# oshi-fuse-board-mk-1_3-mini-ato.net
KiCad netlist of a schematic drawn in EAGLE
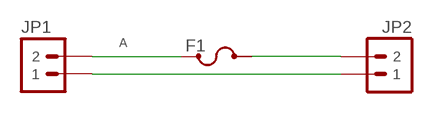
[diagram p0: schematic, sheet 1]

(export (version "E")
  (design (tool "Eeschema 10.0.6"))
  (components
    (comp (ref "F1")
      (value "FUSEMINI-897")
      (footprint "eagle-import:KEYSTONE-MINI-897-FUSE-HOLDER")
      (libsource (lib "eagle-import") (part "FUSEMINI-897"))
    )
    (comp (ref "JP1")
      (value "M025MM")
      (footprint "eagle-import:SCREWTERMINAL-5MM-2")
      (libsource (lib "eagle-import") (part "M025MM"))
    )
    (comp (ref "JP2")
      (value "M025MM")
      (footprint "eagle-import:SCREWTERMINAL-5MM-2")
      (libsource (lib "eagle-import") (part "M025MM"))
    )
  )
  (nets
    (net (code "1") (name "/A") (class "Default")
      (node (ref "F1") (pin "P1@1") (pinfunction "1_P1@1") (pintype "passive"))
      (node (ref "F1") (pin "P1@2") (pinfunction "1_P1@2") (pintype "passive"))
      (node (ref "JP1") (pin "2") (pinfunction "2_2") (pintype "passive"))
    )
    (net (code "2") (name "Net-(F1-2-PadP2@1)") (class "Default")
      (node (ref "F1") (pin "P2@1") (pinfunction "2_P2@1") (pintype "passive"))
      (node (ref "F1") (pin "P2@2") (pinfunction "2_P2@2") (pintype "passive"))
      (node (ref "JP2") (pin "2") (pinfunction "2_2") (pintype "passive"))
    )
    (net (code "3") (name "Net-(JP1-Pad1)") (class "Default")
      (node (ref "JP1") (pin "1") (pinfunction "1_1") (pintype "passive"))
      (node (ref "JP2") (pin "1") (pinfunction "1_1") (pintype "passive"))
    )
  )
)
